# glass_udrive_pcb.net
KiCad netlist of a schematic drawn in EAGLE
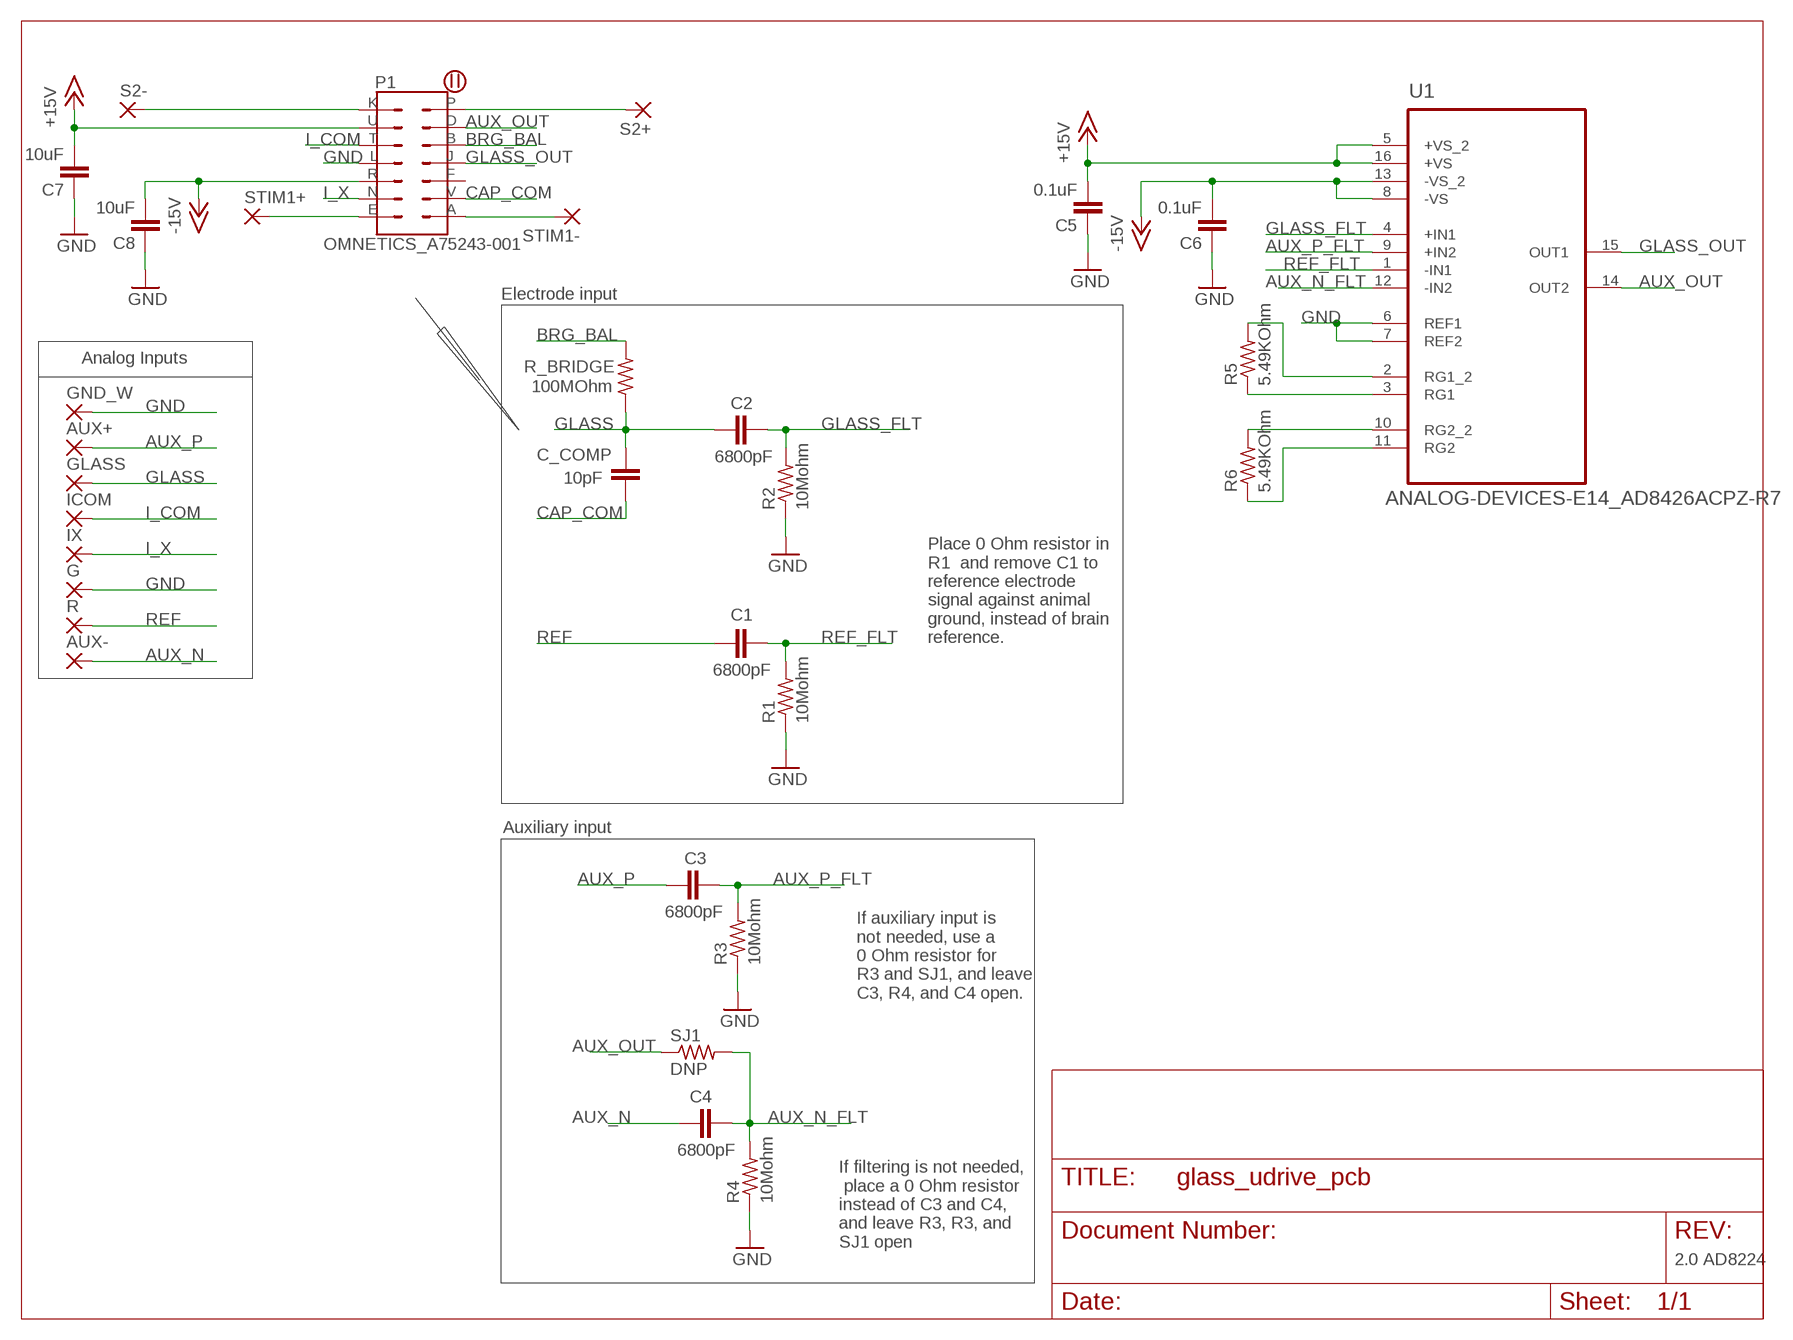
[diagram p0: schematic, sheet 1]

(export (version "E")
  (design (tool "Eeschema 10.0.6"))
  (components
    (comp (ref "AUX+")
      (value "THROUGH-HOLE-30MIL/15MIL")
      (footprint "eagle-import:30MIL_15MIL")
      (libsource (lib "eagle-import") (part "THROUGH-HOLE-30MIL/15MIL"))
    )
    (comp (ref "AUX-")
      (value "THROUGH-HOLE-30MIL/15MIL")
      (footprint "eagle-import:30MIL_15MIL")
      (libsource (lib "eagle-import") (part "THROUGH-HOLE-30MIL/15MIL"))
    )
    (comp (ref "C1")
      (value "6800pF")
      (footprint "eagle-import:0201")
      (libsource (lib "eagle-import") (part "C_0201"))
    )
    (comp (ref "C2")
      (value "6800pF")
      (footprint "eagle-import:0201")
      (libsource (lib "eagle-import") (part "C_0201"))
    )
    (comp (ref "C3")
      (value "6800pF")
      (footprint "eagle-import:0201")
      (libsource (lib "eagle-import") (part "C_0201"))
    )
    (comp (ref "C4")
      (value "6800pF")
      (footprint "eagle-import:0201")
      (libsource (lib "eagle-import") (part "C_0201"))
    )
    (comp (ref "C5")
      (value "0.1uF")
      (footprint "eagle-import:0201")
      (libsource (lib "eagle-import") (part "C_0201"))
    )
    (comp (ref "C6")
      (value "0.1uF")
      (footprint "eagle-import:0201")
      (libsource (lib "eagle-import") (part "C_0201"))
    )
    (comp (ref "C7")
      (value "10uF")
      (footprint "eagle-import:0603")
      (libsource (lib "eagle-import") (part "C_0603"))
    )
    (comp (ref "C8")
      (value "10uF")
      (footprint "eagle-import:0603")
      (libsource (lib "eagle-import") (part "C_0603"))
    )
    (comp (ref "C_COMP")
      (value "10pF")
      (footprint "eagle-import:0402")
      (libsource (lib "eagle-import") (part "C_0402"))
    )
    (comp (ref "G")
      (value "THROUGH-HOLE-30MIL/15MIL")
      (footprint "eagle-import:30MIL_15MIL")
      (libsource (lib "eagle-import") (part "THROUGH-HOLE-30MIL/15MIL"))
    )
    (comp (ref "GLASS")
      (value "THROUGH-HOLE-30MIL/15MIL")
      (footprint "eagle-import:30MIL_15MIL")
      (libsource (lib "eagle-import") (part "THROUGH-HOLE-30MIL/15MIL"))
    )
    (comp (ref "GND_W")
      (value "THROUGH-HOLE-30MIL/15MIL")
      (footprint "eagle-import:30MIL_15MIL")
      (libsource (lib "eagle-import") (part "THROUGH-HOLE-30MIL/15MIL"))
    )
    (comp (ref "ICOM")
      (value "THROUGH-HOLE-30MIL/15MIL")
      (footprint "eagle-import:30MIL_15MIL")
      (libsource (lib "eagle-import") (part "THROUGH-HOLE-30MIL/15MIL"))
    )
    (comp (ref "IX")
      (value "THROUGH-HOLE-30MIL/15MIL")
      (footprint "eagle-import:30MIL_15MIL")
      (libsource (lib "eagle-import") (part "THROUGH-HOLE-30MIL/15MIL"))
    )
    (comp (ref "P1")
      (value "OMNETICS_A75243-001")
      (footprint "eagle-import:OMNETICS_A75243-001")
      (libsource (lib "eagle-import") (part "OMNETICS_A75243-001"))
    )
    (comp (ref "R")
      (value "THROUGH-HOLE-30MIL/15MIL")
      (footprint "eagle-import:30MIL_15MIL")
      (libsource (lib "eagle-import") (part "THROUGH-HOLE-30MIL/15MIL"))
    )
    (comp (ref "R1")
      (value "10Mohm")
      (footprint "eagle-import:0201")
      (libsource (lib "eagle-import") (part "R_0201"))
    )
    (comp (ref "R2")
      (value "10Mohm")
      (footprint "eagle-import:0201")
      (libsource (lib "eagle-import") (part "R_0201"))
    )
    (comp (ref "R3")
      (value "10Mohm")
      (footprint "eagle-import:0201")
      (libsource (lib "eagle-import") (part "R_0201"))
    )
    (comp (ref "R4")
      (value "10Mohm")
      (footprint "eagle-import:0201")
      (libsource (lib "eagle-import") (part "R_0201"))
    )
    (comp (ref "R5")
      (value "5.49KOhm")
      (footprint "eagle-import:0201")
      (libsource (lib "eagle-import") (part "R_0201"))
    )
    (comp (ref "R6")
      (value "5.49KOhm")
      (footprint "eagle-import:0201")
      (libsource (lib "eagle-import") (part "R_0201"))
    )
    (comp (ref "R_BRIDGE")
      (value "100MOhm")
      (footprint "eagle-import:0402")
      (libsource (lib "eagle-import") (part "R_0402"))
    )
    (comp (ref "S2+")
      (value "THROUGH-HOLE-30MIL/15MIL")
      (footprint "eagle-import:30MIL_15MIL")
      (libsource (lib "eagle-import") (part "THROUGH-HOLE-30MIL/15MIL"))
    )
    (comp (ref "S2-")
      (value "THROUGH-HOLE-30MIL/15MIL")
      (footprint "eagle-import:30MIL_15MIL")
      (libsource (lib "eagle-import") (part "THROUGH-HOLE-30MIL/15MIL"))
    )
    (comp (ref "SJ1")
      (value "DNP")
      (footprint "eagle-import:0201")
      (libsource (lib "eagle-import") (part "R_0201"))
    )
    (comp (ref "STIM1+")
      (value "THROUGH-HOLE-30MIL/15MIL")
      (footprint "eagle-import:30MIL_15MIL")
      (libsource (lib "eagle-import") (part "THROUGH-HOLE-30MIL/15MIL"))
    )
    (comp (ref "STIM1-")
      (value "THROUGH-HOLE-30MIL/15MIL")
      (footprint "eagle-import:30MIL_15MIL")
      (libsource (lib "eagle-import") (part "THROUGH-HOLE-30MIL/15MIL"))
    )
    (comp (ref "U1")
      (value "ANALOG-DEVICES-E14_AD8426ACPZ-R7")
      (footprint "eagle-import:ANALOG-DEVICES-E14_QFN65P400X400X100-16N")
      (fields (field (name "MPN") "AD8426ACPZ-R7"))
      (libsource (lib "eagle-import") (part "ANALOG-DEVICES-E14_AD8426ACPZ-R7"))
    )
  )
  (nets
    (net (code "1") (name "+15V") (class "Default")
      (node (ref "C5") (pin "2") (pinfunction "2_2") (pintype "passive"))
      (node (ref "C7") (pin "2") (pinfunction "2_2") (pintype "passive"))
      (node (ref "P1") (pin "U") (pinfunction "U_U") (pintype "passive"))
      (node (ref "U1") (pin "16") (pinfunction "+VS_16") (pintype "passive"))
      (node (ref "U1") (pin "5") (pinfunction "+VS_2_5") (pintype "passive"))
    )
    (net (code "2") (name "-15V") (class "Default")
      (node (ref "C6") (pin "2") (pinfunction "2_2") (pintype "passive"))
      (node (ref "C8") (pin "2") (pinfunction "2_2") (pintype "passive"))
      (node (ref "P1") (pin "R") (pinfunction "R_R") (pintype "passive"))
      (node (ref "U1") (pin "13") (pinfunction "-VS_2_13") (pintype "passive"))
      (node (ref "U1") (pin "8") (pinfunction "-VS_8") (pintype "passive"))
    )
    (net (code "3") (name "/AUX_N") (class "Default")
      (node (ref "AUX-") (pin "P$1") (pinfunction "P_P$1") (pintype "passive"))
      (node (ref "C4") (pin "1") (pinfunction "1_1") (pintype "passive"))
    )
    (net (code "4") (name "/AUX_N_FLT") (class "Default")
      (node (ref "C4") (pin "2") (pinfunction "2_2") (pintype "passive"))
      (node (ref "R4") (pin "2") (pinfunction "2_2") (pintype "passive"))
      (node (ref "SJ1") (pin "2") (pinfunction "2_2") (pintype "passive"))
      (node (ref "U1") (pin "12") (pinfunction "-IN2_12") (pintype "passive"))
    )
    (net (code "5") (name "/AUX_OUT") (class "Default")
      (node (ref "P1") (pin "D") (pinfunction "D_D") (pintype "passive"))
      (node (ref "SJ1") (pin "1") (pinfunction "1_1") (pintype "passive"))
      (node (ref "U1") (pin "14") (pinfunction "OUT2_14") (pintype "passive"))
    )
    (net (code "6") (name "/AUX_P") (class "Default")
      (node (ref "AUX+") (pin "P$1") (pinfunction "P_P$1") (pintype "passive"))
      (node (ref "C3") (pin "1") (pinfunction "1_1") (pintype "passive"))
    )
    (net (code "7") (name "/AUX_P_FLT") (class "Default")
      (node (ref "C3") (pin "2") (pinfunction "2_2") (pintype "passive"))
      (node (ref "R3") (pin "2") (pinfunction "2_2") (pintype "passive"))
      (node (ref "U1") (pin "9") (pinfunction "+IN2_9") (pintype "passive"))
    )
    (net (code "8") (name "/BRG_BAL") (class "Default")
      (node (ref "P1") (pin "B") (pinfunction "B_B") (pintype "passive"))
      (node (ref "R_BRIDGE") (pin "2") (pinfunction "2_2") (pintype "passive"))
    )
    (net (code "9") (name "/CAP_COM") (class "Default")
      (node (ref "C_COMP") (pin "2") (pinfunction "2_2") (pintype "passive"))
      (node (ref "P1") (pin "V") (pinfunction "V_V") (pintype "passive"))
    )
    (net (code "10") (name "/GLASS") (class "Default")
      (node (ref "C2") (pin "1") (pinfunction "1_1") (pintype "passive"))
      (node (ref "C_COMP") (pin "1") (pinfunction "1_1") (pintype "passive"))
      (node (ref "GLASS") (pin "P$1") (pinfunction "P_P$1") (pintype "passive"))
      (node (ref "R_BRIDGE") (pin "1") (pinfunction "1_1") (pintype "passive"))
    )
    (net (code "11") (name "/GLASS_FLT") (class "Default")
      (node (ref "C2") (pin "2") (pinfunction "2_2") (pintype "passive"))
      (node (ref "R2") (pin "2") (pinfunction "2_2") (pintype "passive"))
      (node (ref "U1") (pin "4") (pinfunction "+IN1_4") (pintype "passive"))
    )
    (net (code "12") (name "/GLASS_OUT") (class "Default")
      (node (ref "P1") (pin "J") (pinfunction "J_J") (pintype "passive"))
      (node (ref "U1") (pin "15") (pinfunction "OUT1_15") (pintype "passive"))
    )
    (net (code "13") (name "/I_COM") (class "Default")
      (node (ref "ICOM") (pin "P$1") (pinfunction "P_P$1") (pintype "passive"))
      (node (ref "P1") (pin "T") (pinfunction "T_T") (pintype "passive"))
    )
    (net (code "14") (name "/I_X") (class "Default")
      (node (ref "IX") (pin "P$1") (pinfunction "P_P$1") (pintype "passive"))
      (node (ref "P1") (pin "N") (pinfunction "N_N") (pintype "passive"))
    )
    (net (code "15") (name "/REF") (class "Default")
      (node (ref "C1") (pin "1") (pinfunction "1_1") (pintype "passive"))
      (node (ref "R") (pin "P$1") (pinfunction "P_P$1") (pintype "passive"))
    )
    (net (code "16") (name "/REF_FLT") (class "Default")
      (node (ref "C1") (pin "2") (pinfunction "2_2") (pintype "passive"))
      (node (ref "R1") (pin "2") (pinfunction "2_2") (pintype "passive"))
      (node (ref "U1") (pin "1") (pinfunction "-IN1_1") (pintype "passive"))
    )
    (net (code "17") (name "GND") (class "Default")
      (node (ref "C5") (pin "1") (pinfunction "1_1") (pintype "passive"))
      (node (ref "C6") (pin "1") (pinfunction "1_1") (pintype "passive"))
      (node (ref "C7") (pin "1") (pinfunction "1_1") (pintype "passive"))
      (node (ref "C8") (pin "1") (pinfunction "1_1") (pintype "passive"))
      (node (ref "G") (pin "P$1") (pinfunction "P_P$1") (pintype "passive"))
      (node (ref "GND_W") (pin "P$1") (pinfunction "P_P$1") (pintype "passive"))
      (node (ref "P1") (pin "L") (pinfunction "L_L") (pintype "passive"))
      (node (ref "R1") (pin "1") (pinfunction "1_1") (pintype "passive"))
      (node (ref "R2") (pin "1") (pinfunction "1_1") (pintype "passive"))
      (node (ref "R3") (pin "1") (pinfunction "1_1") (pintype "passive"))
      (node (ref "R4") (pin "1") (pinfunction "1_1") (pintype "passive"))
      (node (ref "U1") (pin "6") (pinfunction "REF1_6") (pintype "passive"))
      (node (ref "U1") (pin "7") (pinfunction "REF2_7") (pintype "passive"))
    )
    (net (code "18") (name "Net-(S2+-P)") (class "Default")
      (node (ref "P1") (pin "P") (pinfunction "P_P") (pintype "passive"))
      (node (ref "S2+") (pin "P$1") (pinfunction "P_P$1") (pintype "passive"))
    )
    (net (code "19") (name "Net-(S2--P)") (class "Default")
      (node (ref "P1") (pin "K") (pinfunction "K_K") (pintype "passive"))
      (node (ref "S2-") (pin "P$1") (pinfunction "P_P$1") (pintype "passive"))
    )
    (net (code "20") (name "Net-(STIM1+-P)") (class "Default")
      (node (ref "P1") (pin "E") (pinfunction "E_E") (pintype "passive"))
      (node (ref "STIM1+") (pin "P$1") (pinfunction "P_P$1") (pintype "passive"))
    )
    (net (code "21") (name "Net-(STIM1--P)") (class "Default")
      (node (ref "P1") (pin "A") (pinfunction "A_A") (pintype "passive"))
      (node (ref "STIM1-") (pin "P$1") (pinfunction "P_P$1") (pintype "passive"))
    )
    (net (code "22") (name "Net-(U1-RG1)") (class "Default")
      (node (ref "R5") (pin "1") (pinfunction "1_1") (pintype "passive"))
      (node (ref "U1") (pin "3") (pinfunction "RG1_3") (pintype "passive"))
    )
    (net (code "23") (name "Net-(U1-RG1_2)") (class "Default")
      (node (ref "R5") (pin "2") (pinfunction "2_2") (pintype "passive"))
      (node (ref "U1") (pin "2") (pinfunction "RG1_2_2") (pintype "passive"))
    )
    (net (code "24") (name "Net-(U1-RG2)") (class "Default")
      (node (ref "R6") (pin "1") (pinfunction "1_1") (pintype "passive"))
      (node (ref "U1") (pin "11") (pinfunction "RG2_11") (pintype "passive"))
    )
    (net (code "25") (name "Net-(U1-RG2_2)") (class "Default")
      (node (ref "R6") (pin "2") (pinfunction "2_2") (pintype "passive"))
      (node (ref "U1") (pin "10") (pinfunction "RG2_2_10") (pintype "passive"))
    )
    (net (code "26") (name "unconnected-(P1-PadF)") (class "Default")
      (node (ref "P1") (pin "F") (pinfunction "F_F") (pintype "passive"))
    )
  )
)
